# OutputStage.net
KiCad netlist of a schematic drawn in Altium Designer
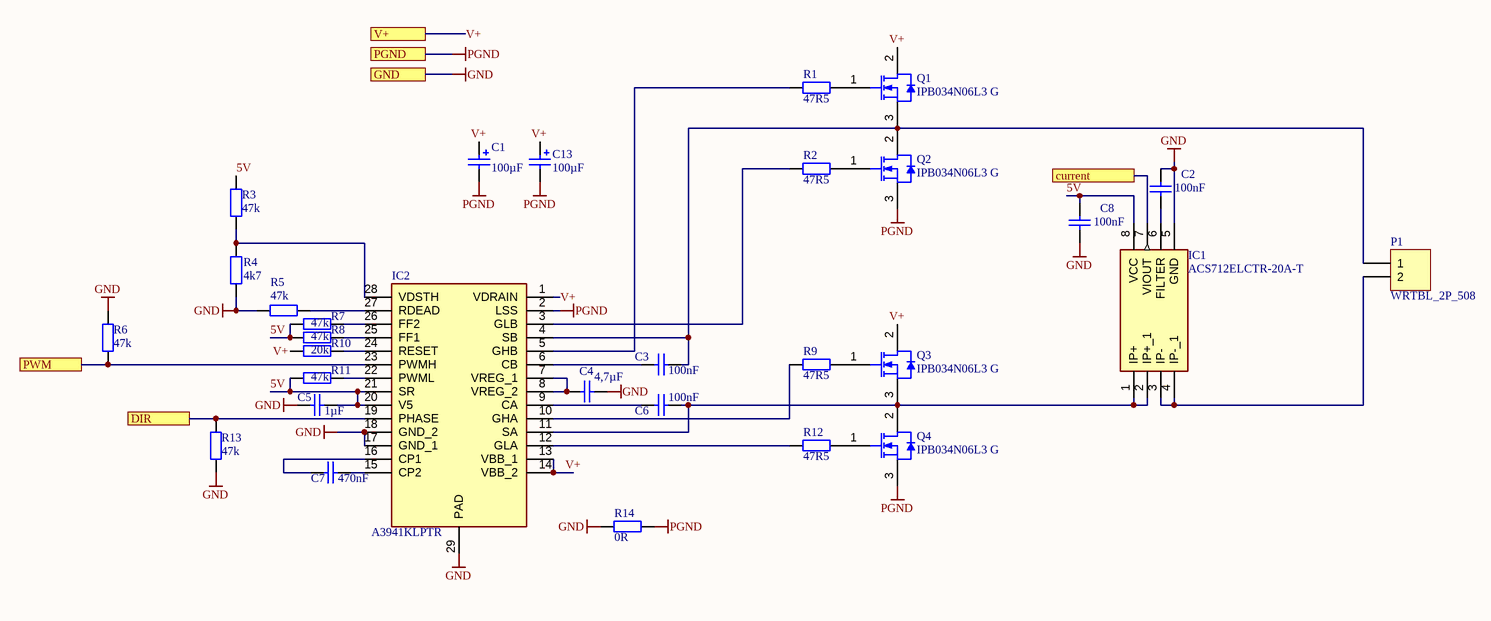
[diagram p0: OutputStage.SchDoc]

(export (version "E")
  (design (tool "Eeschema 10.0.6"))
  (components
    (comp (ref "C1")
      (value "100µF")
      (footprint "Cap_THT_Elko_rad_D8mm")
      (fields (field (name "VOLTAGE") "35V"))
      (libsource (lib "MCI_ALTIUM_LIB") (part "Cap_pol"))
    )
    (comp (ref "C2")
      (value "100nF")
      (footprint "_0603")
      (libsource (lib "MCI_ALTIUM_LIB") (part "Cap_nopol"))
    )
    (comp (ref "C3")
      (value "100nF")
      (footprint "_0603")
      (libsource (lib "MCI_ALTIUM_LIB") (part "Cap_nopol"))
    )
    (comp (ref "C4")
      (value "4,7µF")
      (footprint "_0603")
      (libsource (lib "MCI_ALTIUM_LIB") (part "Cap_nopol"))
    )
    (comp (ref "C5") (value "1µF") (footprint "_0805") (libsource (lib "MCI_ALTIUM_LIB") (part "Cap_nopol")))
    (comp (ref "C6")
      (value "100nF")
      (footprint "_0603")
      (libsource (lib "MCI_ALTIUM_LIB") (part "Cap_nopol"))
    )
    (comp (ref "C7")
      (value "470nF")
      (footprint "_0603")
      (libsource (lib "MCI_ALTIUM_LIB") (part "Cap_nopol"))
    )
    (comp (ref "C8")
      (value "100nF")
      (footprint "_0603")
      (libsource (lib "MCI_ALTIUM_LIB") (part "Cap_nopol"))
    )
    (comp (ref "C13")
      (value "100µF")
      (footprint "Cap_THT_Elko_rad_D8mm")
      (fields (field (name "VOLTAGE") "35V"))
      (libsource (lib "MCI_ALTIUM_LIB") (part "Cap_pol"))
    )
    (comp (ref "IC1")
      (value "ACS712ELCTR-20A-T")
      (footprint "SOIC127P600X175-8N")
      (description "Integrated Circuit")
      (fields (field (name "RS PART NUMBER") "6807135P"))
      (libsource (lib "Project_library") (part "ACS712ELCTR-20A-T"))
    )
    (comp (ref "IC2")
      (value "A3941KLPTR")
      (footprint "SOP65P640X120-29N")
      (description "Integrated Circuit")
      (fields (field (name "RS PART NUMBER") "7248704P"))
      (libsource (lib "Project_library") (part "A3941KLPTR"))
    )
    (comp (ref "P1")
      (value "WRTBL_2P_508")
      (footprint "WRTBL_2P_508")
      (libsource (lib "MCI_ALTIUM_LIB") (part "Header 2"))
    )
    (comp (ref "Q1")
      (value "IPB034N06L3 G")
      (footprint "INF-PG-TO-263-3-2_A_N")
      (fields (field (name "MANUFACTURER") "Infineon"))
      (libsource (lib "Project_library") (part "IPB034N06L3 G"))
    )
    (comp (ref "Q2")
      (value "IPB034N06L3 G")
      (footprint "INF-PG-TO-263-3-2_A_N")
      (fields (field (name "MANUFACTURER") "Infineon"))
      (libsource (lib "Project_library") (part "IPB034N06L3 G"))
    )
    (comp (ref "Q3")
      (value "IPB034N06L3 G")
      (footprint "INF-PG-TO-263-3-2_A_N")
      (fields (field (name "MANUFACTURER") "Infineon"))
      (libsource (lib "Project_library") (part "IPB034N06L3 G"))
    )
    (comp (ref "Q4")
      (value "IPB034N06L3 G")
      (footprint "INF-PG-TO-263-3-2_A_N")
      (fields (field (name "MANUFACTURER") "Infineon"))
      (libsource (lib "Project_library") (part "IPB034N06L3 G"))
    )
    (comp (ref "R1")
      (value "47R5")
      (footprint "_0603")
      (libsource (lib "MCI_ALTIUM_LIB") (part "Res_normal"))
    )
    (comp (ref "R2")
      (value "47R5")
      (footprint "_0603")
      (libsource (lib "MCI_ALTIUM_LIB") (part "Res_normal"))
    )
    (comp (ref "R3") (value "47k") (footprint "_0603") (libsource (lib "") (part "Res_normal_1")))
    (comp (ref "R4") (value "4k7") (footprint "_0603") (libsource (lib "") (part "Res_normal_1")))
    (comp (ref "R5") (value "47k") (footprint "_0603") (libsource (lib "MCI_ALTIUM_LIB") (part "Res_normal")))
    (comp (ref "R6") (value "47k") (footprint "_0603") (libsource (lib "") (part "Res_normal_1")))
    (comp (ref "R7") (value "47k") (footprint "_0603") (libsource (lib "MCI_ALTIUM_LIB") (part "Res_normal")))
    (comp (ref "R8") (value "47k") (footprint "_0603") (libsource (lib "MCI_ALTIUM_LIB") (part "Res_normal")))
    (comp (ref "R9")
      (value "47R5")
      (footprint "_0603")
      (libsource (lib "MCI_ALTIUM_LIB") (part "Res_normal"))
    )
    (comp (ref "R10")
      (value "20k")
      (footprint "_0603")
      (libsource (lib "MCI_ALTIUM_LIB") (part "Res_normal"))
    )
    (comp (ref "R11")
      (value "47k")
      (footprint "_0603")
      (libsource (lib "MCI_ALTIUM_LIB") (part "Res_normal"))
    )
    (comp (ref "R12")
      (value "47R5")
      (footprint "_0603")
      (libsource (lib "MCI_ALTIUM_LIB") (part "Res_normal"))
    )
    (comp (ref "R13") (value "47k") (footprint "_0603") (libsource (lib "") (part "Res_normal_1")))
    (comp (ref "R14") (value "0R") (footprint "_0603") (libsource (lib "MCI_ALTIUM_LIB") (part "Res_normal")))
  )
  (nets
    (net (code "1") (name "/5V") (class "Default")
      (node (ref "C5") (pin "2") (pinfunction "2_2") (pintype "passive"))
      (node (ref "C8") (pin "2") (pinfunction "2_2") (pintype "passive"))
      (node (ref "IC1") (pin "8") (pinfunction "VCC_8") (pintype "power_in"))
      (node (ref "IC2") (pin "20") (pinfunction "V5_20") (pintype "passive"))
      (node (ref "IC2") (pin "21") (pinfunction "SR_21") (pintype "passive"))
      (node (ref "R11") (pin "2") (pinfunction "2_2") (pintype "passive"))
      (node (ref "R3") (pin "1") (pinfunction "1_1") (pintype "passive"))
      (node (ref "R7") (pin "2") (pinfunction "2_2") (pintype "passive"))
      (node (ref "R8") (pin "2") (pinfunction "2_2") (pintype "passive"))
    )
    (net (code "2") (name "/DIR") (class "Default")
      (node (ref "IC2") (pin "19") (pinfunction "PHASE_19") (pintype "passive"))
      (node (ref "R13") (pin "1") (pinfunction "1_1") (pintype "passive"))
    )
    (net (code "3") (name "/PWM") (class "Default")
      (node (ref "IC2") (pin "23") (pinfunction "PWMH_23") (pintype "passive"))
      (node (ref "R6") (pin "2") (pinfunction "2_2") (pintype "passive"))
    )
    (net (code "4") (name "/V+") (class "Default")
      (node (ref "C1") (pin "1") (pinfunction "1_1") (pintype "passive"))
      (node (ref "C13") (pin "1") (pinfunction "1_1") (pintype "passive"))
      (node (ref "IC2") (pin "1") (pinfunction "VDRAIN_1") (pintype "passive"))
      (node (ref "IC2") (pin "13") (pinfunction "VBB_1_13") (pintype "passive"))
      (node (ref "IC2") (pin "14") (pinfunction "VBB_2_14") (pintype "passive"))
      (node (ref "Q1") (pin "2") (pinfunction "DRAIN_2") (pintype "passive"))
      (node (ref "Q3") (pin "2") (pinfunction "DRAIN_2") (pintype "passive"))
      (node (ref "R10") (pin "2") (pinfunction "2_2") (pintype "passive"))
    )
    (net (code "5") (name "/current") (class "Default")
      (node (ref "IC1") (pin "7") (pinfunction "VIOUT_7") (pintype "output"))
    )
    (net (code "6") (name "GND") (class "Default")
      (node (ref "C2") (pin "2") (pinfunction "2_2") (pintype "passive"))
      (node (ref "C4") (pin "2") (pinfunction "2_2") (pintype "passive"))
      (node (ref "C5") (pin "1") (pinfunction "1_1") (pintype "passive"))
      (node (ref "C8") (pin "1") (pinfunction "1_1") (pintype "passive"))
      (node (ref "IC1") (pin "5") (pinfunction "GND_5") (pintype "power_in"))
      (node (ref "IC2") (pin "17") (pinfunction "GND_1_17") (pintype "passive"))
      (node (ref "IC2") (pin "18") (pinfunction "GND_2_18") (pintype "passive"))
      (node (ref "IC2") (pin "29") (pinfunction "PAD_29") (pintype "passive"))
      (node (ref "R13") (pin "2") (pinfunction "2_2") (pintype "passive"))
      (node (ref "R14") (pin "2") (pinfunction "2_2") (pintype "passive"))
      (node (ref "R4") (pin "2") (pinfunction "2_2") (pintype "passive"))
      (node (ref "R5") (pin "2") (pinfunction "2_2") (pintype "passive"))
      (node (ref "R6") (pin "1") (pinfunction "1_1") (pintype "passive"))
    )
    (net (code "7") (name "Net-(IC1-FILTER)") (class "Default")
      (node (ref "C2") (pin "1") (pinfunction "1_1") (pintype "passive"))
      (node (ref "IC1") (pin "6") (pinfunction "FILTER_6") (pintype "passive"))
    )
    (net (code "8") (name "Net-(IC1-IP+)") (class "Default")
      (node (ref "C6") (pin "2") (pinfunction "2_2") (pintype "passive"))
      (node (ref "IC1") (pin "1") (pinfunction "IP+_1") (pintype "passive"))
      (node (ref "IC1") (pin "2") (pinfunction "IP+_1_2") (pintype "passive"))
      (node (ref "IC2") (pin "11") (pinfunction "SA_11") (pintype "passive"))
      (node (ref "Q3") (pin "3") (pinfunction "SOURCE_3") (pintype "passive"))
      (node (ref "Q4") (pin "2") (pinfunction "DRAIN_2") (pintype "passive"))
    )
    (net (code "9") (name "Net-(IC1-IP-)") (class "Default")
      (node (ref "IC1") (pin "3") (pinfunction "IP-_3") (pintype "passive"))
      (node (ref "IC1") (pin "4") (pinfunction "IP-_1_4") (pintype "passive"))
      (node (ref "P1") (pin "2") (pinfunction "2_2") (pintype "passive"))
    )
    (net (code "10") (name "Net-(IC2-CA)") (class "Default")
      (node (ref "C6") (pin "1") (pinfunction "1_1") (pintype "passive"))
      (node (ref "IC2") (pin "9") (pinfunction "CA_9") (pintype "passive"))
    )
    (net (code "11") (name "Net-(IC2-CB)") (class "Default")
      (node (ref "C3") (pin "1") (pinfunction "1_1") (pintype "passive"))
      (node (ref "IC2") (pin "6") (pinfunction "CB_6") (pintype "passive"))
    )
    (net (code "12") (name "Net-(IC2-CP1)") (class "Default")
      (node (ref "C7") (pin "1") (pinfunction "1_1") (pintype "passive"))
      (node (ref "IC2") (pin "16") (pinfunction "CP1_16") (pintype "passive"))
    )
    (net (code "13") (name "Net-(IC2-CP2)") (class "Default")
      (node (ref "C7") (pin "2") (pinfunction "2_2") (pintype "passive"))
      (node (ref "IC2") (pin "15") (pinfunction "CP2_15") (pintype "passive"))
    )
    (net (code "14") (name "Net-(IC2-FF1)") (class "Default")
      (node (ref "IC2") (pin "25") (pinfunction "FF1_25") (pintype "passive"))
      (node (ref "R8") (pin "1") (pinfunction "1_1") (pintype "passive"))
    )
    (net (code "15") (name "Net-(IC2-FF2)") (class "Default")
      (node (ref "IC2") (pin "26") (pinfunction "FF2_26") (pintype "passive"))
      (node (ref "R7") (pin "1") (pinfunction "1_1") (pintype "passive"))
    )
    (net (code "16") (name "Net-(IC2-GHA)") (class "Default")
      (node (ref "IC2") (pin "10") (pinfunction "GHA_10") (pintype "passive"))
      (node (ref "R9") (pin "2") (pinfunction "2_2") (pintype "passive"))
    )
    (net (code "17") (name "Net-(IC2-GHB)") (class "Default")
      (node (ref "IC2") (pin "5") (pinfunction "GHB_5") (pintype "passive"))
      (node (ref "R1") (pin "2") (pinfunction "2_2") (pintype "passive"))
    )
    (net (code "18") (name "Net-(IC2-GLA)") (class "Default")
      (node (ref "IC2") (pin "12") (pinfunction "GLA_12") (pintype "passive"))
      (node (ref "R12") (pin "2") (pinfunction "2_2") (pintype "passive"))
    )
    (net (code "19") (name "Net-(IC2-GLB)") (class "Default")
      (node (ref "IC2") (pin "3") (pinfunction "GLB_3") (pintype "passive"))
      (node (ref "R2") (pin "2") (pinfunction "2_2") (pintype "passive"))
    )
    (net (code "20") (name "Net-(IC2-PWML)") (class "Default")
      (node (ref "IC2") (pin "22") (pinfunction "PWML_22") (pintype "passive"))
      (node (ref "R11") (pin "1") (pinfunction "1_1") (pintype "passive"))
    )
    (net (code "21") (name "Net-(IC2-RDEAD)") (class "Default")
      (node (ref "IC2") (pin "27") (pinfunction "RDEAD_27") (pintype "passive"))
      (node (ref "R5") (pin "1") (pinfunction "1_1") (pintype "passive"))
    )
    (net (code "22") (name "Net-(IC2-RESET)") (class "Default")
      (node (ref "IC2") (pin "24") (pinfunction "RESET_24") (pintype "passive"))
      (node (ref "R10") (pin "1") (pinfunction "1_1") (pintype "passive"))
    )
    (net (code "23") (name "Net-(IC2-SB)") (class "Default")
      (node (ref "C3") (pin "2") (pinfunction "2_2") (pintype "passive"))
      (node (ref "IC2") (pin "4") (pinfunction "SB_4") (pintype "passive"))
      (node (ref "P1") (pin "1") (pinfunction "1_1") (pintype "passive"))
      (node (ref "Q1") (pin "3") (pinfunction "SOURCE_3") (pintype "passive"))
      (node (ref "Q2") (pin "2") (pinfunction "DRAIN_2") (pintype "passive"))
    )
    (net (code "24") (name "Net-(IC2-VDSTH)") (class "Default")
      (node (ref "IC2") (pin "28") (pinfunction "VDSTH_28") (pintype "passive"))
      (node (ref "R3") (pin "2") (pinfunction "2_2") (pintype "passive"))
      (node (ref "R4") (pin "1") (pinfunction "1_1") (pintype "passive"))
    )
    (net (code "25") (name "Net-(IC2-VREG_1)") (class "Default")
      (node (ref "C4") (pin "1") (pinfunction "1_1") (pintype "passive"))
      (node (ref "IC2") (pin "7") (pinfunction "VREG_1_7") (pintype "passive"))
      (node (ref "IC2") (pin "8") (pinfunction "VREG_2_8") (pintype "passive"))
    )
    (net (code "26") (name "Net-(Q1-GATE)") (class "Default")
      (node (ref "Q1") (pin "1") (pinfunction "GATE_1") (pintype "passive"))
      (node (ref "R1") (pin "1") (pinfunction "1_1") (pintype "passive"))
    )
    (net (code "27") (name "Net-(Q2-GATE)") (class "Default")
      (node (ref "Q2") (pin "1") (pinfunction "GATE_1") (pintype "passive"))
      (node (ref "R2") (pin "1") (pinfunction "1_1") (pintype "passive"))
    )
    (net (code "28") (name "Net-(Q3-GATE)") (class "Default")
      (node (ref "Q3") (pin "1") (pinfunction "GATE_1") (pintype "passive"))
      (node (ref "R9") (pin "1") (pinfunction "1_1") (pintype "passive"))
    )
    (net (code "29") (name "Net-(Q4-GATE)") (class "Default")
      (node (ref "Q4") (pin "1") (pinfunction "GATE_1") (pintype "passive"))
      (node (ref "R12") (pin "1") (pinfunction "1_1") (pintype "passive"))
    )
    (net (code "30") (name "PGND") (class "Default")
      (node (ref "C1") (pin "2") (pinfunction "2_2") (pintype "passive"))
      (node (ref "C13") (pin "2") (pinfunction "2_2") (pintype "passive"))
      (node (ref "IC2") (pin "2") (pinfunction "LSS_2") (pintype "passive"))
      (node (ref "Q2") (pin "3") (pinfunction "SOURCE_3") (pintype "passive"))
      (node (ref "Q4") (pin "3") (pinfunction "SOURCE_3") (pintype "passive"))
      (node (ref "R14") (pin "1") (pinfunction "1_1") (pintype "passive"))
    )
  )
)
